# PERIPHERALS.net
KiCad netlist of a schematic drawn in Altium Designer
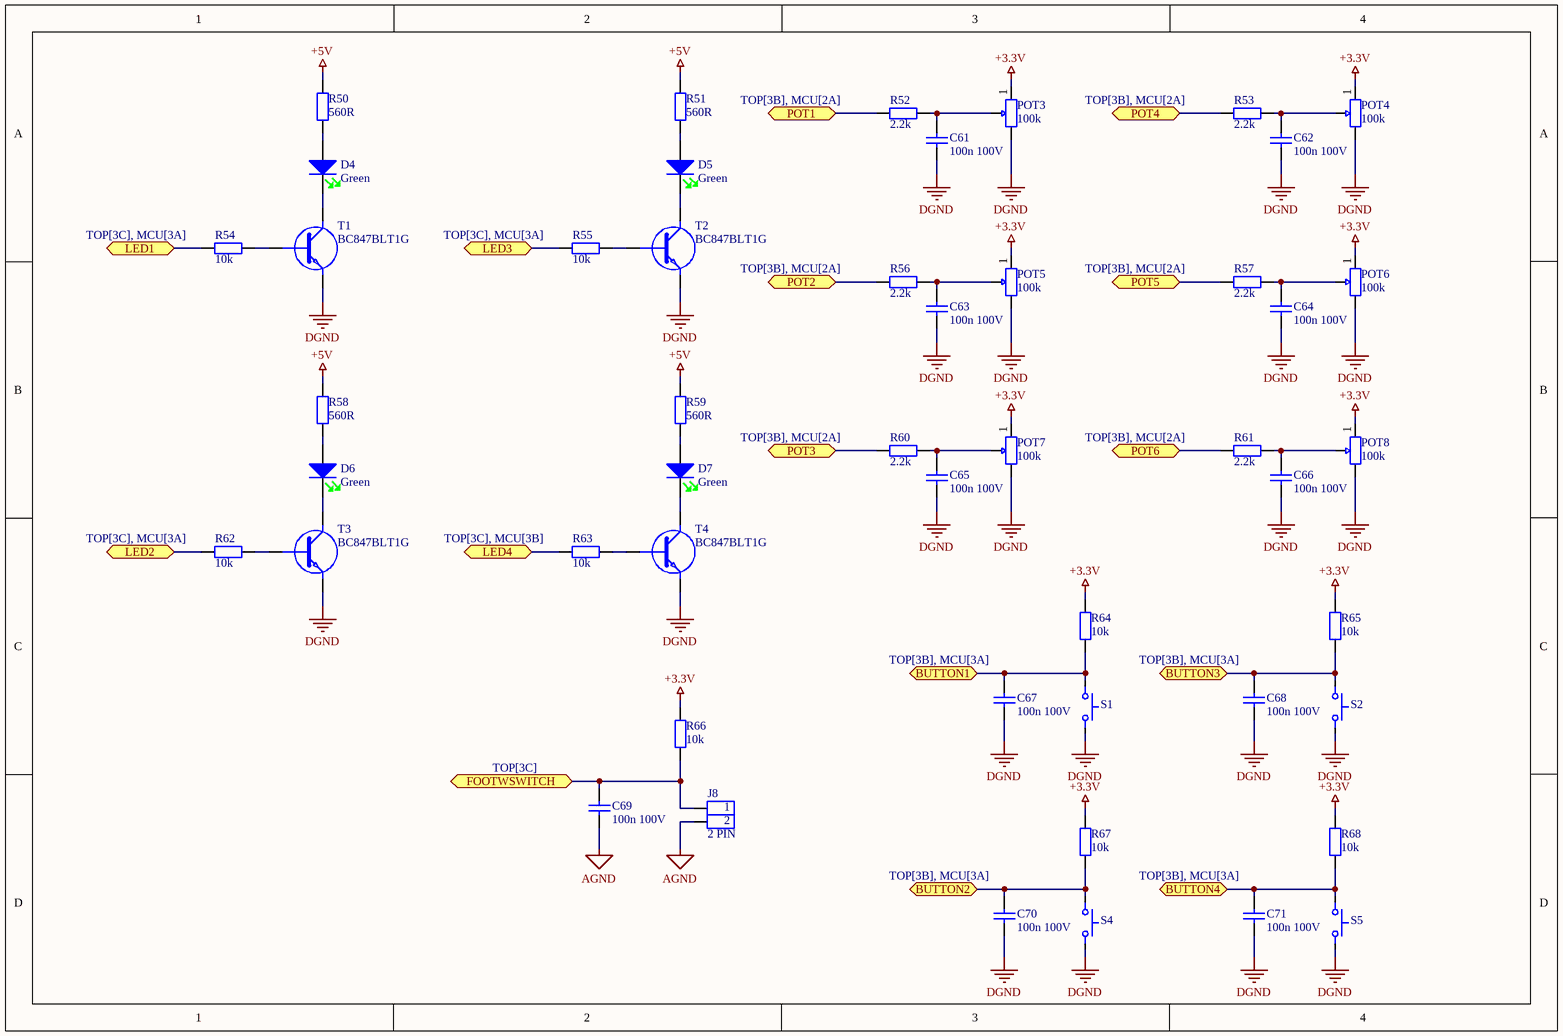
[diagram p0: PERIPHERALS.SchDoc]

(export (version "E")
  (design (tool "Eeschema 10.0.6"))
  (components
    (comp (ref "C61")
      (value "100n 100V")
      (footprint "FOOTPRINTS:CAPACITOR 0805")
      (description "Capacitor: ceramic; MLCC; 100nF; 100V; X7R; ±10%; SMD; 0805")
      (fields
        (field (name "MANUFACTURER") "YAGEO")
        (field (name "MANUFACTURER PART NUMBER") "CC0805KKX7R0BB104")
      )
      (libsource (lib "SYMBOLS") (part "Capacitor 100n 100V 10% X7R 0805"))
    )
    (comp (ref "C62")
      (value "100n 100V")
      (footprint "FOOTPRINTS:CAPACITOR 0805")
      (description "Capacitor: ceramic; MLCC; 100nF; 100V; X7R; ±10%; SMD; 0805")
      (fields
        (field (name "MANUFACTURER") "YAGEO")
        (field (name "MANUFACTURER PART NUMBER") "CC0805KKX7R0BB104")
      )
      (libsource (lib "SYMBOLS") (part "Capacitor 100n 100V 10% X7R 0805"))
    )
    (comp (ref "C63")
      (value "100n 100V")
      (footprint "FOOTPRINTS:CAPACITOR 0805")
      (description "Capacitor: ceramic; MLCC; 100nF; 100V; X7R; ±10%; SMD; 0805")
      (fields
        (field (name "MANUFACTURER") "YAGEO")
        (field (name "MANUFACTURER PART NUMBER") "CC0805KKX7R0BB104")
      )
      (libsource (lib "SYMBOLS") (part "Capacitor 100n 100V 10% X7R 0805"))
    )
    (comp (ref "C64")
      (value "100n 100V")
      (footprint "FOOTPRINTS:CAPACITOR 0805")
      (description "Capacitor: ceramic; MLCC; 100nF; 100V; X7R; ±10%; SMD; 0805")
      (fields
        (field (name "MANUFACTURER") "YAGEO")
        (field (name "MANUFACTURER PART NUMBER") "CC0805KKX7R0BB104")
      )
      (libsource (lib "SYMBOLS") (part "Capacitor 100n 100V 10% X7R 0805"))
    )
    (comp (ref "C65")
      (value "100n 100V")
      (footprint "FOOTPRINTS:CAPACITOR 0805")
      (description "Capacitor: ceramic; MLCC; 100nF; 100V; X7R; ±10%; SMD; 0805")
      (fields
        (field (name "MANUFACTURER") "YAGEO")
        (field (name "MANUFACTURER PART NUMBER") "CC0805KKX7R0BB104")
      )
      (libsource (lib "SYMBOLS") (part "Capacitor 100n 100V 10% X7R 0805"))
    )
    (comp (ref "C66")
      (value "100n 100V")
      (footprint "FOOTPRINTS:CAPACITOR 0805")
      (description "Capacitor: ceramic; MLCC; 100nF; 100V; X7R; ±10%; SMD; 0805")
      (fields
        (field (name "MANUFACTURER") "YAGEO")
        (field (name "MANUFACTURER PART NUMBER") "CC0805KKX7R0BB104")
      )
      (libsource (lib "SYMBOLS") (part "Capacitor 100n 100V 10% X7R 0805"))
    )
    (comp (ref "C67")
      (value "100n 100V")
      (footprint "FOOTPRINTS:CAPACITOR 0805")
      (description "Capacitor: ceramic; MLCC; 100nF; 100V; X7R; ±10%; SMD; 0805")
      (fields
        (field (name "MANUFACTURER") "YAGEO")
        (field (name "MANUFACTURER PART NUMBER") "CC0805KKX7R0BB104")
      )
      (libsource (lib "SYMBOLS") (part "Capacitor 100n 100V 10% X7R 0805"))
    )
    (comp (ref "C68")
      (value "100n 100V")
      (footprint "FOOTPRINTS:CAPACITOR 0805")
      (description "Capacitor: ceramic; MLCC; 100nF; 100V; X7R; ±10%; SMD; 0805")
      (fields
        (field (name "MANUFACTURER") "YAGEO")
        (field (name "MANUFACTURER PART NUMBER") "CC0805KKX7R0BB104")
      )
      (libsource (lib "SYMBOLS") (part "Capacitor 100n 100V 10% X7R 0805"))
    )
    (comp (ref "C69")
      (value "100n 100V")
      (footprint "FOOTPRINTS:CAPACITOR 0805")
      (description "Capacitor: ceramic; MLCC; 100nF; 100V; X7R; ±10%; SMD; 0805")
      (fields
        (field (name "MANUFACTURER") "YAGEO")
        (field (name "MANUFACTURER PART NUMBER") "CC0805KKX7R0BB104")
      )
      (libsource (lib "SYMBOLS") (part "Capacitor 100n 100V 10% X7R 0805"))
    )
    (comp (ref "C70")
      (value "100n 100V")
      (footprint "FOOTPRINTS:CAPACITOR 0805")
      (description "Capacitor: ceramic; MLCC; 100nF; 100V; X7R; ±10%; SMD; 0805")
      (fields
        (field (name "MANUFACTURER") "YAGEO")
        (field (name "MANUFACTURER PART NUMBER") "CC0805KKX7R0BB104")
      )
      (libsource (lib "SYMBOLS") (part "Capacitor 100n 100V 10% X7R 0805"))
    )
    (comp (ref "C71")
      (value "100n 100V")
      (footprint "FOOTPRINTS:CAPACITOR 0805")
      (description "Capacitor: ceramic; MLCC; 100nF; 100V; X7R; ±10%; SMD; 0805")
      (fields
        (field (name "MANUFACTURER") "YAGEO")
        (field (name "MANUFACTURER PART NUMBER") "CC0805KKX7R0BB104")
      )
      (libsource (lib "SYMBOLS") (part "Capacitor 100n 100V 10% X7R 0805"))
    )
    (comp (ref "D4")
      (value "Green")
      (footprint "FOOTPRINTS:LED 3MM GREEN")
      (libsource (lib "SYMBOLS") (part "Diode LED Green 3mm THT SMD 20mA"))
    )
    (comp (ref "D5")
      (value "Green")
      (footprint "FOOTPRINTS:LED 3MM GREEN")
      (libsource (lib "SYMBOLS") (part "Diode LED Green 3mm THT SMD 20mA"))
    )
    (comp (ref "D6")
      (value "Green")
      (footprint "FOOTPRINTS:LED 3MM GREEN")
      (libsource (lib "SYMBOLS") (part "Diode LED Green 3mm THT SMD 20mA"))
    )
    (comp (ref "D7")
      (value "Green")
      (footprint "FOOTPRINTS:LED 3MM GREEN")
      (libsource (lib "SYMBOLS") (part "Diode LED Green 3mm THT SMD 20mA"))
    )
    (comp (ref "J8")
      (value "2 PIN")
      (footprint "FOOTPRINTS:MECHANICAL PINHEADER 2P 2.54MM MALE")
      (description "Headers & Wire Housings 2.54MM CGRIDIII HDR 2P VERT SR SEL AU")
      (fields (field (name "MANUFACTURER") "Molex") (field (name "MANUFACTURER PART NUMBER") "90120-0762"))
      (libsource (lib "SYMBOLS") (part "Mechanical Pinheader Male 2pin P=2.54mm THT"))
    )
    (comp (ref "POT3")
      (value "100k")
      (footprint "FOOTPRINTS:POTENTIOMETER PTV09A W\\H")
      (description "Potentiometers 100K 20% 9MM CARBON POT")
      (fields
        (field (name "MANUFACTURER") "Bourns")
        (field (name "MANUFACTURER PART NUMBER") "PTV09A-4020U-B104")
      )
      (libsource (lib "SYMBOLS") (part "Potentiometer PCB 100k THT Linear PTV09A"))
    )
    (comp (ref "POT4")
      (value "100k")
      (footprint "FOOTPRINTS:POTENTIOMETER PTV09A W\\H")
      (description "Potentiometers 100K 20% 9MM CARBON POT")
      (fields
        (field (name "MANUFACTURER") "Bourns")
        (field (name "MANUFACTURER PART NUMBER") "PTV09A-4020U-B104")
      )
      (libsource (lib "SYMBOLS") (part "Potentiometer PCB 100k THT Linear PTV09A"))
    )
    (comp (ref "POT5")
      (value "100k")
      (footprint "FOOTPRINTS:POTENTIOMETER PTV09A W\\H")
      (description "Potentiometers 100K 20% 9MM CARBON POT")
      (fields
        (field (name "MANUFACTURER") "Bourns")
        (field (name "MANUFACTURER PART NUMBER") "PTV09A-4020U-B104")
      )
      (libsource (lib "SYMBOLS") (part "Potentiometer PCB 100k THT Linear PTV09A"))
    )
    (comp (ref "POT6")
      (value "100k")
      (footprint "FOOTPRINTS:POTENTIOMETER PTV09A W\\H")
      (description "Potentiometers 100K 20% 9MM CARBON POT")
      (fields
        (field (name "MANUFACTURER") "Bourns")
        (field (name "MANUFACTURER PART NUMBER") "PTV09A-4020U-B104")
      )
      (libsource (lib "SYMBOLS") (part "Potentiometer PCB 100k THT Linear PTV09A"))
    )
    (comp (ref "POT7")
      (value "100k")
      (footprint "FOOTPRINTS:POTENTIOMETER PTV09A W\\H")
      (description "Potentiometers 100K 20% 9MM CARBON POT")
      (fields
        (field (name "MANUFACTURER") "Bourns")
        (field (name "MANUFACTURER PART NUMBER") "PTV09A-4020U-B104")
      )
      (libsource (lib "SYMBOLS") (part "Potentiometer PCB 100k THT Linear PTV09A"))
    )
    (comp (ref "POT8")
      (value "100k")
      (footprint "FOOTPRINTS:POTENTIOMETER PTV09A W\\H")
      (description "Potentiometers 100K 20% 9MM CARBON POT")
      (fields
        (field (name "MANUFACTURER") "Bourns")
        (field (name "MANUFACTURER PART NUMBER") "PTV09A-4020U-B104")
      )
      (libsource (lib "SYMBOLS") (part "Potentiometer PCB 100k THT Linear PTV09A"))
    )
    (comp (ref "R50")
      (value "560R")
      (footprint "FOOTPRINTS:RESISTOR 0805")
      (description "Resistor: thick film; SMD; 0805; 560Ω; 0.125W; ±1%; -55÷155°C")
      (fields
        (field (name "MANUFACTURER") "Yageo")
        (field (name "MANUFACTURER PART NUMBER") "RC0805FR-07560R")
      )
      (libsource (lib "SYMBOLS") (part "Resistor 560R 1% 1/8W 0805"))
    )
    (comp (ref "R51")
      (value "560R")
      (footprint "FOOTPRINTS:RESISTOR 0805")
      (description "Resistor: thick film; SMD; 0805; 560Ω; 0.125W; ±1%; -55÷155°C")
      (fields
        (field (name "MANUFACTURER") "Yageo")
        (field (name "MANUFACTURER PART NUMBER") "RC0805FR-07560R")
      )
      (libsource (lib "SYMBOLS") (part "Resistor 560R 1% 1/8W 0805"))
    )
    (comp (ref "R52")
      (value "2.2k")
      (footprint "FOOTPRINTS:RESISTOR 0805")
      (description "Resistor: thick film; SMD; 0805; 2.2kΩ; 0.125W; ±1%; -55÷155°C")
      (fields
        (field (name "MANUFACTURER") "Yageo")
        (field (name "MANUFACTURER PART NUMBER") "RC0805FR-072K2")
      )
      (libsource (lib "SYMBOLS") (part "Resistor 2.2k 1% 1/8W 0805"))
    )
    (comp (ref "R53")
      (value "2.2k")
      (footprint "FOOTPRINTS:RESISTOR 0805")
      (description "Resistor: thick film; SMD; 0805; 2.2kΩ; 0.125W; ±1%; -55÷155°C")
      (fields
        (field (name "MANUFACTURER") "Yageo")
        (field (name "MANUFACTURER PART NUMBER") "RC0805FR-072K2")
      )
      (libsource (lib "SYMBOLS") (part "Resistor 2.2k 1% 1/8W 0805"))
    )
    (comp (ref "R54")
      (value "10k")
      (footprint "FOOTPRINTS:RESISTOR 0805")
      (description "Resistor: thick film; SMD; 0805; 10kΩ; 0.125W; ±1%; -55÷155°C")
      (fields
        (field (name "MANUFACTURER") "Yageo")
        (field (name "MANUFACTURER PART NUMBER") "RC0805FR-0710K")
      )
      (libsource (lib "") (part "Resistor 10k 1% 1/8W 0805_1"))
    )
    (comp (ref "R55")
      (value "10k")
      (footprint "FOOTPRINTS:RESISTOR 0805")
      (description "Resistor: thick film; SMD; 0805; 10kΩ; 0.125W; ±1%; -55÷155°C")
      (fields
        (field (name "MANUFACTURER") "Yageo")
        (field (name "MANUFACTURER PART NUMBER") "RC0805FR-0710K")
      )
      (libsource (lib "") (part "Resistor 10k 1% 1/8W 0805_1"))
    )
    (comp (ref "R56")
      (value "2.2k")
      (footprint "FOOTPRINTS:RESISTOR 0805")
      (description "Resistor: thick film; SMD; 0805; 2.2kΩ; 0.125W; ±1%; -55÷155°C")
      (fields
        (field (name "MANUFACTURER") "Yageo")
        (field (name "MANUFACTURER PART NUMBER") "RC0805FR-072K2")
      )
      (libsource (lib "SYMBOLS") (part "Resistor 2.2k 1% 1/8W 0805"))
    )
    (comp (ref "R57")
      (value "2.2k")
      (footprint "FOOTPRINTS:RESISTOR 0805")
      (description "Resistor: thick film; SMD; 0805; 2.2kΩ; 0.125W; ±1%; -55÷155°C")
      (fields
        (field (name "MANUFACTURER") "Yageo")
        (field (name "MANUFACTURER PART NUMBER") "RC0805FR-072K2")
      )
      (libsource (lib "SYMBOLS") (part "Resistor 2.2k 1% 1/8W 0805"))
    )
    (comp (ref "R58")
      (value "560R")
      (footprint "FOOTPRINTS:RESISTOR 0805")
      (description "Resistor: thick film; SMD; 0805; 560Ω; 0.125W; ±1%; -55÷155°C")
      (fields
        (field (name "MANUFACTURER") "Yageo")
        (field (name "MANUFACTURER PART NUMBER") "RC0805FR-07560R")
      )
      (libsource (lib "SYMBOLS") (part "Resistor 560R 1% 1/8W 0805"))
    )
    (comp (ref "R59")
      (value "560R")
      (footprint "FOOTPRINTS:RESISTOR 0805")
      (description "Resistor: thick film; SMD; 0805; 560Ω; 0.125W; ±1%; -55÷155°C")
      (fields
        (field (name "MANUFACTURER") "Yageo")
        (field (name "MANUFACTURER PART NUMBER") "RC0805FR-07560R")
      )
      (libsource (lib "SYMBOLS") (part "Resistor 560R 1% 1/8W 0805"))
    )
    (comp (ref "R60")
      (value "2.2k")
      (footprint "FOOTPRINTS:RESISTOR 0805")
      (description "Resistor: thick film; SMD; 0805; 2.2kΩ; 0.125W; ±1%; -55÷155°C")
      (fields
        (field (name "MANUFACTURER") "Yageo")
        (field (name "MANUFACTURER PART NUMBER") "RC0805FR-072K2")
      )
      (libsource (lib "SYMBOLS") (part "Resistor 2.2k 1% 1/8W 0805"))
    )
    (comp (ref "R61")
      (value "2.2k")
      (footprint "FOOTPRINTS:RESISTOR 0805")
      (description "Resistor: thick film; SMD; 0805; 2.2kΩ; 0.125W; ±1%; -55÷155°C")
      (fields
        (field (name "MANUFACTURER") "Yageo")
        (field (name "MANUFACTURER PART NUMBER") "RC0805FR-072K2")
      )
      (libsource (lib "SYMBOLS") (part "Resistor 2.2k 1% 1/8W 0805"))
    )
    (comp (ref "R62")
      (value "10k")
      (footprint "FOOTPRINTS:RESISTOR 0805")
      (description "Resistor: thick film; SMD; 0805; 10kΩ; 0.125W; ±1%; -55÷155°C")
      (fields
        (field (name "MANUFACTURER") "Yageo")
        (field (name "MANUFACTURER PART NUMBER") "RC0805FR-0710K")
      )
      (libsource (lib "") (part "Resistor 10k 1% 1/8W 0805_1"))
    )
    (comp (ref "R63")
      (value "10k")
      (footprint "FOOTPRINTS:RESISTOR 0805")
      (description "Resistor: thick film; SMD; 0805; 10kΩ; 0.125W; ±1%; -55÷155°C")
      (fields
        (field (name "MANUFACTURER") "Yageo")
        (field (name "MANUFACTURER PART NUMBER") "RC0805FR-0710K")
      )
      (libsource (lib "") (part "Resistor 10k 1% 1/8W 0805_1"))
    )
    (comp (ref "R64")
      (value "10k")
      (footprint "FOOTPRINTS:RESISTOR 0805")
      (description "Resistor: thick film; SMD; 0805; 10kΩ; 0.125W; ±1%; -55÷155°C")
      (fields
        (field (name "MANUFACTURER") "Yageo")
        (field (name "MANUFACTURER PART NUMBER") "RC0805FR-0710K")
      )
      (libsource (lib "SYMBOLS") (part "Resistor 10k 1% 1/8W 0805"))
    )
    (comp (ref "R65")
      (value "10k")
      (footprint "FOOTPRINTS:RESISTOR 0805")
      (description "Resistor: thick film; SMD; 0805; 10kΩ; 0.125W; ±1%; -55÷155°C")
      (fields
        (field (name "MANUFACTURER") "Yageo")
        (field (name "MANUFACTURER PART NUMBER") "RC0805FR-0710K")
      )
      (libsource (lib "SYMBOLS") (part "Resistor 10k 1% 1/8W 0805"))
    )
    (comp (ref "R66")
      (value "10k")
      (footprint "FOOTPRINTS:RESISTOR 0805")
      (description "Resistor: thick film; SMD; 0805; 10kΩ; 0.125W; ±1%; -55÷155°C")
      (fields
        (field (name "MANUFACTURER") "Yageo")
        (field (name "MANUFACTURER PART NUMBER") "RC0805FR-0710K")
      )
      (libsource (lib "SYMBOLS") (part "Resistor 10k 1% 1/8W 0805"))
    )
    (comp (ref "R67")
      (value "10k")
      (footprint "FOOTPRINTS:RESISTOR 0805")
      (description "Resistor: thick film; SMD; 0805; 10kΩ; 0.125W; ±1%; -55÷155°C")
      (fields
        (field (name "MANUFACTURER") "Yageo")
        (field (name "MANUFACTURER PART NUMBER") "RC0805FR-0710K")
      )
      (libsource (lib "SYMBOLS") (part "Resistor 10k 1% 1/8W 0805"))
    )
    (comp (ref "R68")
      (value "10k")
      (footprint "FOOTPRINTS:RESISTOR 0805")
      (description "Resistor: thick film; SMD; 0805; 10kΩ; 0.125W; ±1%; -55÷155°C")
      (fields
        (field (name "MANUFACTURER") "Yageo")
        (field (name "MANUFACTURER PART NUMBER") "RC0805FR-0710K")
      )
      (libsource (lib "SYMBOLS") (part "Resistor 10k 1% 1/8W 0805"))
    )
    (comp (ref "S1")
      (value "6x6mm")
      (footprint "FOOTPRINTS:MECHANICAL TACTSWITCH SMD 6x6")
      (description "Tactile Switches 6 x 6 mm, 5 mm Act Height, 260 gf, Black, Short Crimped, Through Hole, SPST")
      (fields
        (field (name "MANUFACTURER") "CUI Devices")
        (field (name "MANUFACTURER PART NUMBER") "TS02-66-50-BK-260-SCR-D")
      )
      (libsource (lib "SYMBOLS") (part "Mechanical Tact Switch 6x6mm THT"))
    )
    (comp (ref "S2")
      (value "6x6mm")
      (footprint "FOOTPRINTS:MECHANICAL TACTSWITCH SMD 6x6")
      (description "Tactile Switches 6 x 6 mm, 5 mm Act Height, 260 gf, Black, Short Crimped, Through Hole, SPST")
      (fields
        (field (name "MANUFACTURER") "CUI Devices")
        (field (name "MANUFACTURER PART NUMBER") "TS02-66-50-BK-260-SCR-D")
      )
      (libsource (lib "SYMBOLS") (part "Mechanical Tact Switch 6x6mm THT"))
    )
    (comp (ref "S4")
      (value "6x6mm")
      (footprint "FOOTPRINTS:MECHANICAL TACTSWITCH SMD 6x6")
      (description "Tactile Switches 6 x 6 mm, 5 mm Act Height, 260 gf, Black, Short Crimped, Through Hole, SPST")
      (fields
        (field (name "MANUFACTURER") "CUI Devices")
        (field (name "MANUFACTURER PART NUMBER") "TS02-66-50-BK-260-SCR-D")
      )
      (libsource (lib "SYMBOLS") (part "Mechanical Tact Switch 6x6mm THT"))
    )
    (comp (ref "S5")
      (value "6x6mm")
      (footprint "FOOTPRINTS:MECHANICAL TACTSWITCH SMD 6x6")
      (description "Tactile Switches 6 x 6 mm, 5 mm Act Height, 260 gf, Black, Short Crimped, Through Hole, SPST")
      (fields
        (field (name "MANUFACTURER") "CUI Devices")
        (field (name "MANUFACTURER PART NUMBER") "TS02-66-50-BK-260-SCR-D")
      )
      (libsource (lib "SYMBOLS") (part "Mechanical Tact Switch 6x6mm THT"))
    )
    (comp (ref "T1")
      (value "BC847BLT1G")
      (footprint "FOOTPRINTS:SOT23-3")
      (description "Bipolar Transistors - BJT 100mA 50V NPN")
      (fields (field (name "MANUFACTURER") "onsemi"))
      (libsource (lib "SYMBOLS") (part "Transistor NPN 100mA 50V BC847BLT1G"))
    )
    (comp (ref "T2")
      (value "BC847BLT1G")
      (footprint "FOOTPRINTS:SOT23-3")
      (description "Bipolar Transistors - BJT 100mA 50V NPN")
      (fields (field (name "MANUFACTURER") "onsemi"))
      (libsource (lib "SYMBOLS") (part "Transistor NPN 100mA 50V BC847BLT1G"))
    )
    (comp (ref "T3")
      (value "BC847BLT1G")
      (footprint "FOOTPRINTS:SOT23-3")
      (description "Bipolar Transistors - BJT 100mA 50V NPN")
      (fields (field (name "MANUFACTURER") "onsemi"))
      (libsource (lib "SYMBOLS") (part "Transistor NPN 100mA 50V BC847BLT1G"))
    )
    (comp (ref "T4")
      (value "BC847BLT1G")
      (footprint "FOOTPRINTS:SOT23-3")
      (description "Bipolar Transistors - BJT 100mA 50V NPN")
      (fields (field (name "MANUFACTURER") "onsemi"))
      (libsource (lib "SYMBOLS") (part "Transistor NPN 100mA 50V BC847BLT1G"))
    )
  )
  (nets
    (net (code "1") (name "+3.3V") (class "Default")
      (node (ref "POT3") (pin "1") (pinfunction "1_1") (pintype "passive"))
      (node (ref "POT4") (pin "1") (pinfunction "1_1") (pintype "passive"))
      (node (ref "POT5") (pin "1") (pinfunction "1_1") (pintype "passive"))
      (node (ref "POT6") (pin "1") (pinfunction "1_1") (pintype "passive"))
      (node (ref "POT7") (pin "1") (pinfunction "1_1") (pintype "passive"))
      (node (ref "POT8") (pin "1") (pinfunction "1_1") (pintype "passive"))
      (node (ref "R64") (pin "2") (pinfunction "2_2") (pintype "passive"))
      (node (ref "R65") (pin "2") (pinfunction "2_2") (pintype "passive"))
      (node (ref "R66") (pin "2") (pinfunction "2_2") (pintype "passive"))
      (node (ref "R67") (pin "2") (pinfunction "2_2") (pintype "passive"))
      (node (ref "R68") (pin "2") (pinfunction "2_2") (pintype "passive"))
    )
    (net (code "2") (name "+5V") (class "Default")
      (node (ref "R50") (pin "2") (pinfunction "2_2") (pintype "passive"))
      (node (ref "R51") (pin "2") (pinfunction "2_2") (pintype "passive"))
      (node (ref "R58") (pin "2") (pinfunction "2_2") (pintype "passive"))
      (node (ref "R59") (pin "2") (pinfunction "2_2") (pintype "passive"))
    )
    (net (code "3") (name "/BUTTON1") (class "Default")
      (node (ref "C67") (pin "2") (pinfunction "2_2") (pintype "passive"))
      (node (ref "R64") (pin "1") (pinfunction "1_1") (pintype "passive"))
      (node (ref "S1") (pin "1") (pinfunction "1_1") (pintype "passive"))
    )
    (net (code "4") (name "/BUTTON2") (class "Default")
      (node (ref "C70") (pin "2") (pinfunction "2_2") (pintype "passive"))
      (node (ref "R67") (pin "1") (pinfunction "1_1") (pintype "passive"))
      (node (ref "S4") (pin "1") (pinfunction "1_1") (pintype "passive"))
    )
    (net (code "5") (name "/BUTTON3") (class "Default")
      (node (ref "C68") (pin "2") (pinfunction "2_2") (pintype "passive"))
      (node (ref "R65") (pin "1") (pinfunction "1_1") (pintype "passive"))
      (node (ref "S2") (pin "1") (pinfunction "1_1") (pintype "passive"))
    )
    (net (code "6") (name "/BUTTON4") (class "Default")
      (node (ref "C71") (pin "2") (pinfunction "2_2") (pintype "passive"))
      (node (ref "R68") (pin "1") (pinfunction "1_1") (pintype "passive"))
      (node (ref "S5") (pin "1") (pinfunction "1_1") (pintype "passive"))
    )
    (net (code "7") (name "/FOOTWSWITCH") (class "Default")
      (node (ref "C69") (pin "2") (pinfunction "2_2") (pintype "passive"))
      (node (ref "J8") (pin "1") (pinfunction "1_1") (pintype "passive"))
      (node (ref "R66") (pin "1") (pinfunction "1_1") (pintype "passive"))
    )
    (net (code "8") (name "/LED1") (class "Default")
      (node (ref "R54") (pin "1") (pinfunction "1_1") (pintype "passive"))
    )
    (net (code "9") (name "/LED2") (class "Default")
      (node (ref "R62") (pin "1") (pinfunction "1_1") (pintype "passive"))
    )
    (net (code "10") (name "/LED3") (class "Default")
      (node (ref "R55") (pin "1") (pinfunction "1_1") (pintype "passive"))
    )
    (net (code "11") (name "/LED4") (class "Default")
      (node (ref "R63") (pin "1") (pinfunction "1_1") (pintype "passive"))
    )
    (net (code "12") (name "/POT1") (class "Default")
      (node (ref "R52") (pin "1") (pinfunction "1_1") (pintype "passive"))
    )
    (net (code "13") (name "/POT2") (class "Default")
      (node (ref "R56") (pin "1") (pinfunction "1_1") (pintype "passive"))
    )
    (net (code "14") (name "/POT3") (class "Default")
      (node (ref "R60") (pin "1") (pinfunction "1_1") (pintype "passive"))
    )
    (net (code "15") (name "/POT4") (class "Default")
      (node (ref "R53") (pin "1") (pinfunction "1_1") (pintype "passive"))
    )
    (net (code "16") (name "/POT5") (class "Default")
      (node (ref "R57") (pin "1") (pinfunction "1_1") (pintype "passive"))
    )
    (net (code "17") (name "/POT6") (class "Default")
      (node (ref "R61") (pin "1") (pinfunction "1_1") (pintype "passive"))
    )
    (net (code "18") (name "AGND") (class "Default")
      (node (ref "C69") (pin "1") (pinfunction "1_1") (pintype "passive"))
      (node (ref "J8") (pin "2") (pinfunction "2_2") (pintype "passive"))
    )
    (net (code "19") (name "DGND") (class "Default")
      (node (ref "C61") (pin "1") (pinfunction "1_1") (pintype "passive"))
      (node (ref "C62") (pin "1") (pinfunction "1_1") (pintype "passive"))
      (node (ref "C63") (pin "1") (pinfunction "1_1") (pintype "passive"))
      (node (ref "C64") (pin "1") (pinfunction "1_1") (pintype "passive"))
      (node (ref "C65") (pin "1") (pinfunction "1_1") (pintype "passive"))
      (node (ref "C66") (pin "1") (pinfunction "1_1") (pintype "passive"))
      (node (ref "C67") (pin "1") (pinfunction "1_1") (pintype "passive"))
      (node (ref "C68") (pin "1") (pinfunction "1_1") (pintype "passive"))
      (node (ref "C70") (pin "1") (pinfunction "1_1") (pintype "passive"))
      (node (ref "C71") (pin "1") (pinfunction "1_1") (pintype "passive"))
      (node (ref "POT3") (pin "3") (pinfunction "3_3") (pintype "passive"))
      (node (ref "POT4") (pin "3") (pinfunction "3_3") (pintype "passive"))
      (node (ref "POT5") (pin "3") (pinfunction "3_3") (pintype "passive"))
      (node (ref "POT6") (pin "3") (pinfunction "3_3") (pintype "passive"))
      (node (ref "POT7") (pin "3") (pinfunction "3_3") (pintype "passive"))
      (node (ref "POT8") (pin "3") (pinfunction "3_3") (pintype "passive"))
      (node (ref "S1") (pin "2") (pinfunction "2_2") (pintype "passive"))
      (node (ref "S2") (pin "2") (pinfunction "2_2") (pintype "passive"))
      (node (ref "S4") (pin "2") (pinfunction "2_2") (pintype "passive"))
      (node (ref "S5") (pin "2") (pinfunction "2_2") (pintype "passive"))
      (node (ref "T1") (pin "2") (pinfunction "E_2") (pintype "passive"))
      (node (ref "T2") (pin "2") (pinfunction "E_2") (pintype "passive"))
      (node (ref "T3") (pin "2") (pinfunction "E_2") (pintype "passive"))
      (node (ref "T4") (pin "2") (pinfunction "E_2") (pintype "passive"))
    )
    (net (code "20") (name "Net-(C61-Pad2)") (class "Default")
      (node (ref "C61") (pin "2") (pinfunction "2_2") (pintype "passive"))
      (node (ref "POT3") (pin "2") (pinfunction "2_2") (pintype "passive"))
      (node (ref "R52") (pin "2") (pinfunction "2_2") (pintype "passive"))
    )
    (net (code "21") (name "Net-(C62-Pad2)") (class "Default")
      (node (ref "C62") (pin "2") (pinfunction "2_2") (pintype "passive"))
      (node (ref "POT4") (pin "2") (pinfunction "2_2") (pintype "passive"))
      (node (ref "R53") (pin "2") (pinfunction "2_2") (pintype "passive"))
    )
    (net (code "22") (name "Net-(C63-Pad2)") (class "Default")
      (node (ref "C63") (pin "2") (pinfunction "2_2") (pintype "passive"))
      (node (ref "POT5") (pin "2") (pinfunction "2_2") (pintype "passive"))
      (node (ref "R56") (pin "2") (pinfunction "2_2") (pintype "passive"))
    )
    (net (code "23") (name "Net-(C64-Pad2)") (class "Default")
      (node (ref "C64") (pin "2") (pinfunction "2_2") (pintype "passive"))
      (node (ref "POT6") (pin "2") (pinfunction "2_2") (pintype "passive"))
      (node (ref "R57") (pin "2") (pinfunction "2_2") (pintype "passive"))
    )
    (net (code "24") (name "Net-(C65-Pad2)") (class "Default")
      (node (ref "C65") (pin "2") (pinfunction "2_2") (pintype "passive"))
      (node (ref "POT7") (pin "2") (pinfunction "2_2") (pintype "passive"))
      (node (ref "R60") (pin "2") (pinfunction "2_2") (pintype "passive"))
    )
    (net (code "25") (name "Net-(C66-Pad2)") (class "Default")
      (node (ref "C66") (pin "2") (pinfunction "2_2") (pintype "passive"))
      (node (ref "POT8") (pin "2") (pinfunction "2_2") (pintype "passive"))
      (node (ref "R61") (pin "2") (pinfunction "2_2") (pintype "passive"))
    )
    (net (code "26") (name "Net-(D4-Pad1)") (class "Default")
      (node (ref "D4") (pin "1") (pinfunction "1_1") (pintype "passive"))
      (node (ref "R50") (pin "1") (pinfunction "1_1") (pintype "passive"))
    )
    (net (code "27") (name "Net-(D5-Pad1)") (class "Default")
      (node (ref "D5") (pin "1") (pinfunction "1_1") (pintype "passive"))
      (node (ref "R51") (pin "1") (pinfunction "1_1") (pintype "passive"))
    )
    (net (code "28") (name "Net-(D6-Pad1)") (class "Default")
      (node (ref "D6") (pin "1") (pinfunction "1_1") (pintype "passive"))
      (node (ref "R58") (pin "1") (pinfunction "1_1") (pintype "passive"))
    )
    (net (code "29") (name "Net-(D7-Pad1)") (class "Default")
      (node (ref "D7") (pin "1") (pinfunction "1_1") (pintype "passive"))
      (node (ref "R59") (pin "1") (pinfunction "1_1") (pintype "passive"))
    )
    (net (code "30") (name "Net-(T1-B)") (class "Default")
      (node (ref "R54") (pin "2") (pinfunction "2_2") (pintype "passive"))
      (node (ref "T1") (pin "1") (pinfunction "B_1") (pintype "passive"))
    )
    (net (code "31") (name "Net-(T1-C)") (class "Default")
      (node (ref "D4") (pin "2") (pinfunction "2_2") (pintype "passive"))
      (node (ref "T1") (pin "3") (pinfunction "C_3") (pintype "passive"))
    )
    (net (code "32") (name "Net-(T2-B)") (class "Default")
      (node (ref "R55") (pin "2") (pinfunction "2_2") (pintype "passive"))
      (node (ref "T2") (pin "1") (pinfunction "B_1") (pintype "passive"))
    )
    (net (code "33") (name "Net-(T2-C)") (class "Default")
      (node (ref "D5") (pin "2") (pinfunction "2_2") (pintype "passive"))
      (node (ref "T2") (pin "3") (pinfunction "C_3") (pintype "passive"))
    )
    (net (code "34") (name "Net-(T3-B)") (class "Default")
      (node (ref "R62") (pin "2") (pinfunction "2_2") (pintype "passive"))
      (node (ref "T3") (pin "1") (pinfunction "B_1") (pintype "passive"))
    )
    (net (code "35") (name "Net-(T3-C)") (class "Default")
      (node (ref "D6") (pin "2") (pinfunction "2_2") (pintype "passive"))
      (node (ref "T3") (pin "3") (pinfunction "C_3") (pintype "passive"))
    )
    (net (code "36") (name "Net-(T4-B)") (class "Default")
      (node (ref "R63") (pin "2") (pinfunction "2_2") (pintype "passive"))
      (node (ref "T4") (pin "1") (pinfunction "B_1") (pintype "passive"))
    )
    (net (code "37") (name "Net-(T4-C)") (class "Default")
      (node (ref "D7") (pin "2") (pinfunction "2_2") (pintype "passive"))
      (node (ref "T4") (pin "3") (pinfunction "C_3") (pintype "passive"))
    )
  )
)
